# Thermistor_readout.net
KiCad netlist of a schematic drawn in EAGLE
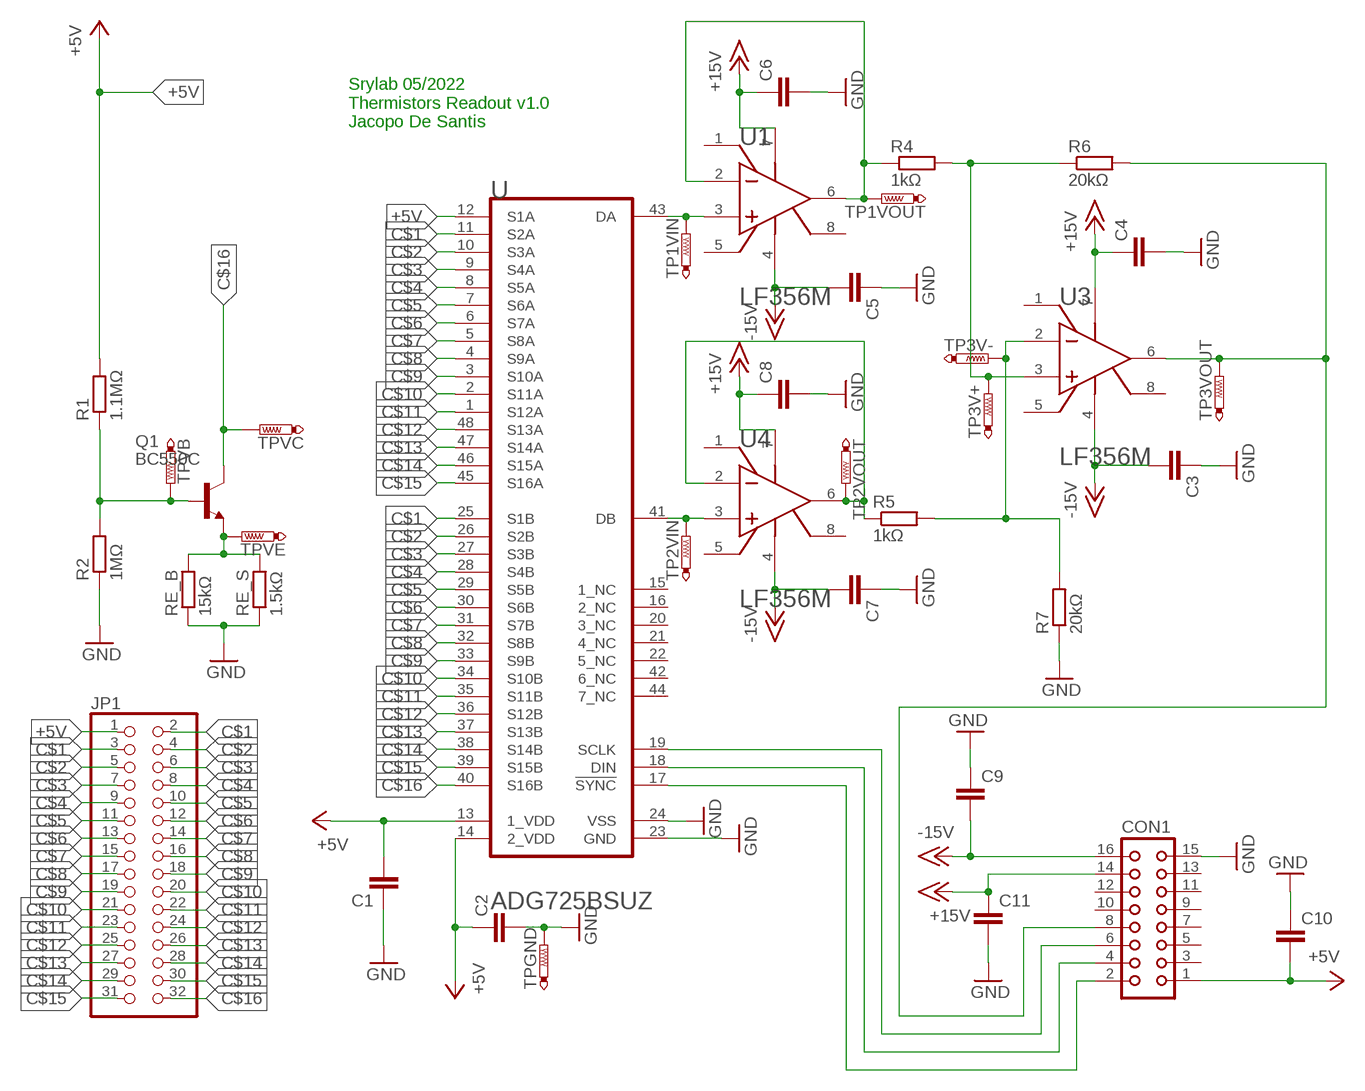
[diagram p0: schematic, sheet 1]

(export (version "E")
  (design (tool "Eeschema 10.0.6"))
  (components
    (comp (ref "C1")
      (value "C-EU_SMDR1206H")
      (footprint "eagle-import:R1206H")
      (libsource (lib "eagle-import") (part "C-EU_SMDR1206H"))
    )
    (comp (ref "C2")
      (value "C-EU_SMDR1206H")
      (footprint "eagle-import:R1206H")
      (libsource (lib "eagle-import") (part "C-EU_SMDR1206H"))
    )
    (comp (ref "C3")
      (value "C-EU_SMDR1206H")
      (footprint "eagle-import:R1206H")
      (libsource (lib "eagle-import") (part "C-EU_SMDR1206H"))
    )
    (comp (ref "C4")
      (value "C-EU_SMDR1206H")
      (footprint "eagle-import:R1206H")
      (libsource (lib "eagle-import") (part "C-EU_SMDR1206H"))
    )
    (comp (ref "C5")
      (value "C-EU_SMDR1206H")
      (footprint "eagle-import:R1206H")
      (libsource (lib "eagle-import") (part "C-EU_SMDR1206H"))
    )
    (comp (ref "C6")
      (value "C-EU_SMDR1206H")
      (footprint "eagle-import:R1206H")
      (libsource (lib "eagle-import") (part "C-EU_SMDR1206H"))
    )
    (comp (ref "C7")
      (value "C-EU_SMDR1206H")
      (footprint "eagle-import:R1206H")
      (libsource (lib "eagle-import") (part "C-EU_SMDR1206H"))
    )
    (comp (ref "C8")
      (value "C-EU_SMDR1206H")
      (footprint "eagle-import:R1206H")
      (libsource (lib "eagle-import") (part "C-EU_SMDR1206H"))
    )
    (comp (ref "C9")
      (value "C-EU_SMDC1206H/D")
      (footprint "eagle-import:C1206H_D")
      (libsource (lib "eagle-import") (part "C-EU_SMDC1206H/D"))
    )
    (comp (ref "C10")
      (value "C-EU_SMDC1206H/D")
      (footprint "eagle-import:C1206H_D")
      (libsource (lib "eagle-import") (part "C-EU_SMDC1206H/D"))
    )
    (comp (ref "C11")
      (value "C-EU_SMDC1206H/D")
      (footprint "eagle-import:C1206H_D")
      (libsource (lib "eagle-import") (part "C-EU_SMDC1206H/D"))
    )
    (comp (ref "CON1")
      (value "CON16L")
      (footprint "eagle-import:CON16L")
      (libsource (lib "eagle-import") (part "CON16L"))
    )
    (comp (ref "JP1")
      (value "PINHD-2X16")
      (footprint "eagle-import:2X16")
      (libsource (lib "eagle-import") (part "PINHD-2X16"))
    )
    (comp (ref "Q1")
      (value "BC550C")
      (footprint "eagle-import:TO92-EBC")
      (libsource (lib "eagle-import") (part "BC550C"))
    )
    (comp (ref "R1")
      (value "1.1ΜΩ")
      (footprint "eagle-import:R0805H")
      (libsource (lib "eagle-import") (part "R-EU_SMD0805H"))
    )
    (comp (ref "R2")
      (value "1ΜΩ")
      (footprint "eagle-import:R0805H")
      (libsource (lib "eagle-import") (part "R-EU_SMD0805H"))
    )
    (comp (ref "R4")
      (value "1kΩ")
      (footprint "eagle-import:R0805H")
      (libsource (lib "eagle-import") (part "R-EU_SMD0805H"))
    )
    (comp (ref "R5")
      (value "1kΩ")
      (footprint "eagle-import:R0805H")
      (libsource (lib "eagle-import") (part "R-EU_SMD0805H"))
    )
    (comp (ref "R6")
      (value "20kΩ")
      (footprint "eagle-import:R0805H")
      (libsource (lib "eagle-import") (part "R-EU_SMD0805H"))
    )
    (comp (ref "R7")
      (value "20kΩ")
      (footprint "eagle-import:R0805H")
      (libsource (lib "eagle-import") (part "R-EU_SMD0805H"))
    )
    (comp (ref "RE_B")
      (value "15kΩ")
      (footprint "eagle-import:R1206H")
      (libsource (lib "eagle-import") (part "R-EU_SMD1206H"))
    )
    (comp (ref "RE_S")
      (value "1.5kΩ")
      (footprint "eagle-import:R0805H")
      (libsource (lib "eagle-import") (part "R-EU_SMD0805H"))
    )
    (comp (ref "TP1VIN")
      (value "PTR1TP20R")
      (footprint "eagle-import:TP20R")
      (libsource (lib "eagle-import") (part "PTR1TP20R"))
    )
    (comp (ref "TP1VOUT")
      (value "PTR1TP20R")
      (footprint "eagle-import:TP20R")
      (libsource (lib "eagle-import") (part "PTR1TP20R"))
    )
    (comp (ref "TP2VIN")
      (value "PTR1TP20R")
      (footprint "eagle-import:TP20R")
      (libsource (lib "eagle-import") (part "PTR1TP20R"))
    )
    (comp (ref "TP2VOUT")
      (value "PTR1TP20R")
      (footprint "eagle-import:TP20R")
      (libsource (lib "eagle-import") (part "PTR1TP20R"))
    )
    (comp (ref "TP3V+")
      (value "PTR1TP20R")
      (footprint "eagle-import:TP20R")
      (libsource (lib "eagle-import") (part "PTR1TP20R"))
    )
    (comp (ref "TP3V-")
      (value "PTR1TP20R")
      (footprint "eagle-import:TP20R")
      (libsource (lib "eagle-import") (part "PTR1TP20R"))
    )
    (comp (ref "TP3VOUT")
      (value "PTR1TP20R")
      (footprint "eagle-import:TP20R")
      (libsource (lib "eagle-import") (part "PTR1TP20R"))
    )
    (comp (ref "TPGND")
      (value "PTR1TP20R")
      (footprint "eagle-import:TP20R")
      (libsource (lib "eagle-import") (part "PTR1TP20R"))
    )
    (comp (ref "TPVB")
      (value "PTR1TP20R")
      (footprint "eagle-import:TP20R")
      (libsource (lib "eagle-import") (part "PTR1TP20R"))
    )
    (comp (ref "TPVC")
      (value "PTR1TP20R")
      (footprint "eagle-import:TP20R")
      (libsource (lib "eagle-import") (part "PTR1TP20R"))
    )
    (comp (ref "TPVE")
      (value "PTR1TP20R")
      (footprint "eagle-import:TP20R")
      (libsource (lib "eagle-import") (part "PTR1TP20R"))
    )
    (comp (ref "U")
      (value "ANALOG_DEVICES_ADG725BSUZANALOG_DEVICES_ADG725BSUZ_0_2")
      (footprint "eagle-import:ANALOG_DEVICES_ADG725BSUZ_2")
      (fields (field (name "MF") "Analog Devices") (field (name "MPN") "ADG725BSUZ"))
      (libsource (lib "eagle-import") (part "ANALOG_DEVICES_ADG725BSUZANALOG_DEVICES_ADG725BSUZ_0_2"))
    )
    (comp (ref "U1")
      (value "TI_NATIONAL_SEMICONDUCTOR_LF356MTI_NATIONAL_SEMICONDUCTOR_LF356M_0_2")
      (footprint "eagle-import:TI_NATIONAL_SEMICONDUCTOR_LF356M_2")
      (fields (field (name "MF") "TI National Semiconductor") (field (name "MPN") "LF356M"))
      (libsource (lib "eagle-import") (part "TI_NATIONAL_SEMICONDUCTOR_LF356MTI_NATIONAL_SEMICONDUCTOR_LF356M_0_2"))
    )
    (comp (ref "U3")
      (value "TI_NATIONAL_SEMICONDUCTOR_LF356MTI_NATIONAL_SEMICONDUCTOR_LF356M_0_2")
      (footprint "eagle-import:TI_NATIONAL_SEMICONDUCTOR_LF356M_2")
      (fields (field (name "MF") "TI National Semiconductor") (field (name "MPN") "LF356M"))
      (libsource (lib "eagle-import") (part "TI_NATIONAL_SEMICONDUCTOR_LF356MTI_NATIONAL_SEMICONDUCTOR_LF356M_0_2"))
    )
    (comp (ref "U4")
      (value "TI_NATIONAL_SEMICONDUCTOR_LF356MTI_NATIONAL_SEMICONDUCTOR_LF356M_0_2")
      (footprint "eagle-import:TI_NATIONAL_SEMICONDUCTOR_LF356M_2")
      (fields (field (name "MF") "TI National Semiconductor") (field (name "MPN") "LF356M"))
      (libsource (lib "eagle-import") (part "TI_NATIONAL_SEMICONDUCTOR_LF356MTI_NATIONAL_SEMICONDUCTOR_LF356M_0_2"))
    )
  )
  (nets
    (net (code "1") (name "+5V") (class "Default")
      (node (ref "C1") (pin "2") (pinfunction "2_2") (pintype "passive"))
      (node (ref "C10") (pin "2") (pinfunction "2_2") (pintype "passive"))
      (node (ref "C2") (pin "1") (pinfunction "1_1") (pintype "passive"))
      (node (ref "CON1") (pin "1") (pinfunction "1_1") (pintype "passive"))
      (node (ref "JP1") (pin "1") (pinfunction "1_1") (pintype "passive"))
      (node (ref "R1") (pin "2") (pinfunction "2_2") (pintype "passive"))
      (node (ref "U") (pin "12") (pinfunction "S1A_12") (pintype "passive"))
      (node (ref "U") (pin "13") (pinfunction "1_VDD_13") (pintype "power_in"))
      (node (ref "U") (pin "14") (pinfunction "2_VDD_14") (pintype "power_in"))
    )
    (net (code "2") (name "+15V") (class "Default")
      (node (ref "C11") (pin "1") (pinfunction "1_1") (pintype "passive"))
      (node (ref "C4") (pin "1") (pinfunction "1_1") (pintype "passive"))
      (node (ref "C6") (pin "1") (pinfunction "1_1") (pintype "passive"))
      (node (ref "C8") (pin "1") (pinfunction "1_1") (pintype "passive"))
      (node (ref "CON1") (pin "14") (pinfunction "14_14") (pintype "passive"))
      (node (ref "U1") (pin "7") (pinfunction "V+_7") (pintype "power_in"))
      (node (ref "U3") (pin "7") (pinfunction "V+_7") (pintype "power_in"))
      (node (ref "U4") (pin "7") (pinfunction "V+_7") (pintype "power_in"))
    )
    (net (code "3") (name "-15V") (class "Default")
      (node (ref "C3") (pin "2") (pinfunction "2_2") (pintype "passive"))
      (node (ref "C5") (pin "2") (pinfunction "2_2") (pintype "passive"))
      (node (ref "C7") (pin "2") (pinfunction "2_2") (pintype "passive"))
      (node (ref "C9") (pin "2") (pinfunction "2_2") (pintype "passive"))
      (node (ref "CON1") (pin "16") (pinfunction "16_16") (pintype "passive"))
      (node (ref "U1") (pin "4") (pinfunction "V-_4") (pintype "power_in"))
      (node (ref "U3") (pin "4") (pinfunction "V-_4") (pintype "power_in"))
      (node (ref "U4") (pin "4") (pinfunction "V-_4") (pintype "power_in"))
    )
    (net (code "4") (name "C$1") (class "Default")
      (node (ref "JP1") (pin "2") (pinfunction "2_2") (pintype "passive"))
      (node (ref "JP1") (pin "3") (pinfunction "3_3") (pintype "passive"))
      (node (ref "U") (pin "11") (pinfunction "S2A_11") (pintype "passive"))
      (node (ref "U") (pin "25") (pinfunction "S1B_25") (pintype "passive"))
    )
    (net (code "5") (name "C$2") (class "Default")
      (node (ref "JP1") (pin "4") (pinfunction "4_4") (pintype "passive"))
      (node (ref "JP1") (pin "5") (pinfunction "5_5") (pintype "passive"))
      (node (ref "U") (pin "10") (pinfunction "S3A_10") (pintype "passive"))
      (node (ref "U") (pin "26") (pinfunction "S2B_26") (pintype "passive"))
    )
    (net (code "6") (name "C$3") (class "Default")
      (node (ref "JP1") (pin "6") (pinfunction "6_6") (pintype "passive"))
      (node (ref "JP1") (pin "7") (pinfunction "7_7") (pintype "passive"))
      (node (ref "U") (pin "27") (pinfunction "S3B_27") (pintype "passive"))
      (node (ref "U") (pin "9") (pinfunction "S4A_9") (pintype "passive"))
    )
    (net (code "7") (name "C$4") (class "Default")
      (node (ref "JP1") (pin "8") (pinfunction "8_8") (pintype "passive"))
      (node (ref "JP1") (pin "9") (pinfunction "9_9") (pintype "passive"))
      (node (ref "U") (pin "28") (pinfunction "S4B_28") (pintype "passive"))
      (node (ref "U") (pin "8") (pinfunction "S5A_8") (pintype "passive"))
    )
    (net (code "8") (name "C$5") (class "Default")
      (node (ref "JP1") (pin "10") (pinfunction "10_10") (pintype "passive"))
      (node (ref "JP1") (pin "11") (pinfunction "11_11") (pintype "passive"))
      (node (ref "U") (pin "29") (pinfunction "S5B_29") (pintype "passive"))
      (node (ref "U") (pin "7") (pinfunction "S6A_7") (pintype "passive"))
    )
    (net (code "9") (name "C$6") (class "Default")
      (node (ref "JP1") (pin "12") (pinfunction "12_12") (pintype "passive"))
      (node (ref "JP1") (pin "13") (pinfunction "13_13") (pintype "passive"))
      (node (ref "U") (pin "30") (pinfunction "S6B_30") (pintype "passive"))
      (node (ref "U") (pin "6") (pinfunction "S7A_6") (pintype "passive"))
    )
    (net (code "10") (name "C$7") (class "Default")
      (node (ref "JP1") (pin "14") (pinfunction "14_14") (pintype "passive"))
      (node (ref "JP1") (pin "15") (pinfunction "15_15") (pintype "passive"))
      (node (ref "U") (pin "31") (pinfunction "S7B_31") (pintype "passive"))
      (node (ref "U") (pin "5") (pinfunction "S8A_5") (pintype "passive"))
    )
    (net (code "11") (name "C$8") (class "Default")
      (node (ref "JP1") (pin "16") (pinfunction "16_16") (pintype "passive"))
      (node (ref "JP1") (pin "17") (pinfunction "17_17") (pintype "passive"))
      (node (ref "U") (pin "32") (pinfunction "S8B_32") (pintype "passive"))
      (node (ref "U") (pin "4") (pinfunction "S9A_4") (pintype "passive"))
    )
    (net (code "12") (name "C$9") (class "Default")
      (node (ref "JP1") (pin "18") (pinfunction "18_18") (pintype "passive"))
      (node (ref "JP1") (pin "19") (pinfunction "19_19") (pintype "passive"))
      (node (ref "U") (pin "3") (pinfunction "S10A_3") (pintype "passive"))
      (node (ref "U") (pin "33") (pinfunction "S9B_33") (pintype "passive"))
    )
    (net (code "13") (name "C$10") (class "Default")
      (node (ref "JP1") (pin "20") (pinfunction "20_20") (pintype "passive"))
      (node (ref "JP1") (pin "21") (pinfunction "21_21") (pintype "passive"))
      (node (ref "U") (pin "2") (pinfunction "S11A_2") (pintype "passive"))
      (node (ref "U") (pin "34") (pinfunction "S10B_34") (pintype "passive"))
    )
    (net (code "14") (name "C$11") (class "Default")
      (node (ref "JP1") (pin "22") (pinfunction "22_22") (pintype "passive"))
      (node (ref "JP1") (pin "23") (pinfunction "23_23") (pintype "passive"))
      (node (ref "U") (pin "1") (pinfunction "S12A_1") (pintype "passive"))
      (node (ref "U") (pin "35") (pinfunction "S11B_35") (pintype "passive"))
    )
    (net (code "15") (name "C$12") (class "Default")
      (node (ref "JP1") (pin "24") (pinfunction "24_24") (pintype "passive"))
      (node (ref "JP1") (pin "25") (pinfunction "25_25") (pintype "passive"))
      (node (ref "U") (pin "36") (pinfunction "S12B_36") (pintype "passive"))
      (node (ref "U") (pin "48") (pinfunction "S13A_48") (pintype "passive"))
    )
    (net (code "16") (name "C$13") (class "Default")
      (node (ref "JP1") (pin "26") (pinfunction "26_26") (pintype "passive"))
      (node (ref "JP1") (pin "27") (pinfunction "27_27") (pintype "passive"))
      (node (ref "U") (pin "37") (pinfunction "S13B_37") (pintype "passive"))
      (node (ref "U") (pin "47") (pinfunction "S14A_47") (pintype "passive"))
    )
    (net (code "17") (name "C$14") (class "Default")
      (node (ref "JP1") (pin "28") (pinfunction "28_28") (pintype "passive"))
      (node (ref "JP1") (pin "29") (pinfunction "29_29") (pintype "passive"))
      (node (ref "U") (pin "38") (pinfunction "S14B_38") (pintype "passive"))
      (node (ref "U") (pin "46") (pinfunction "S15A_46") (pintype "passive"))
    )
    (net (code "18") (name "C$15") (class "Default")
      (node (ref "JP1") (pin "30") (pinfunction "30_30") (pintype "passive"))
      (node (ref "JP1") (pin "31") (pinfunction "31_31") (pintype "passive"))
      (node (ref "U") (pin "39") (pinfunction "S15B_39") (pintype "passive"))
      (node (ref "U") (pin "45") (pinfunction "S16A_45") (pintype "passive"))
    )
    (net (code "19") (name "C$16") (class "Default")
      (node (ref "JP1") (pin "32") (pinfunction "32_32") (pintype "passive"))
      (node (ref "Q1") (pin "C") (pinfunction "C_C") (pintype "passive"))
      (node (ref "TPVC") (pin "TP") (pinfunction "TP_TP") (pintype "input"))
      (node (ref "U") (pin "40") (pinfunction "S16B_40") (pintype "passive"))
    )
    (net (code "20") (name "GND") (class "Default")
      (node (ref "C1") (pin "1") (pinfunction "1_1") (pintype "passive"))
      (node (ref "C10") (pin "1") (pinfunction "1_1") (pintype "passive"))
      (node (ref "C11") (pin "2") (pinfunction "2_2") (pintype "passive"))
      (node (ref "C2") (pin "2") (pinfunction "2_2") (pintype "passive"))
      (node (ref "C3") (pin "1") (pinfunction "1_1") (pintype "passive"))
      (node (ref "C4") (pin "2") (pinfunction "2_2") (pintype "passive"))
      (node (ref "C5") (pin "1") (pinfunction "1_1") (pintype "passive"))
      (node (ref "C6") (pin "2") (pinfunction "2_2") (pintype "passive"))
      (node (ref "C7") (pin "1") (pinfunction "1_1") (pintype "passive"))
      (node (ref "C8") (pin "2") (pinfunction "2_2") (pintype "passive"))
      (node (ref "C9") (pin "1") (pinfunction "1_1") (pintype "passive"))
      (node (ref "CON1") (pin "15") (pinfunction "15_15") (pintype "passive"))
      (node (ref "R2") (pin "1") (pinfunction "1_1") (pintype "passive"))
      (node (ref "R7") (pin "1") (pinfunction "1_1") (pintype "passive"))
      (node (ref "RE_B") (pin "1") (pinfunction "1_1") (pintype "passive"))
      (node (ref "RE_S") (pin "1") (pinfunction "1_1") (pintype "passive"))
      (node (ref "TPGND") (pin "TP") (pinfunction "TP_TP") (pintype "input"))
      (node (ref "U") (pin "23") (pinfunction "GND_23") (pintype "power_in"))
      (node (ref "U") (pin "24") (pinfunction "VSS_24") (pintype "power_in"))
    )
    (net (code "21") (name "Net-(Q1-PadB)") (class "Default")
      (node (ref "Q1") (pin "B") (pinfunction "B_B") (pintype "passive"))
      (node (ref "R1") (pin "1") (pinfunction "1_1") (pintype "passive"))
      (node (ref "R2") (pin "2") (pinfunction "2_2") (pintype "passive"))
      (node (ref "TPVB") (pin "TP") (pinfunction "TP_TP") (pintype "input"))
    )
    (net (code "22") (name "Net-(Q1-PadE)") (class "Default")
      (node (ref "Q1") (pin "E") (pinfunction "E_E") (pintype "passive"))
      (node (ref "RE_B") (pin "2") (pinfunction "2_2") (pintype "passive"))
      (node (ref "RE_S") (pin "2") (pinfunction "2_2") (pintype "passive"))
      (node (ref "TPVE") (pin "TP") (pinfunction "TP_TP") (pintype "input"))
    )
    (net (code "23") (name "Net-(U-DA)") (class "Default")
      (node (ref "TP1VIN") (pin "TP") (pinfunction "TP_TP") (pintype "input"))
      (node (ref "U") (pin "43") (pinfunction "DA_43") (pintype "passive"))
      (node (ref "U1") (pin "3") (pinfunction "IN+_3") (pintype "input"))
    )
    (net (code "24") (name "Net-(U-DB)") (class "Default")
      (node (ref "TP2VIN") (pin "TP") (pinfunction "TP_TP") (pintype "input"))
      (node (ref "U") (pin "41") (pinfunction "DB_41") (pintype "passive"))
      (node (ref "U4") (pin "3") (pinfunction "IN+_3") (pintype "input"))
    )
    (net (code "25") (name "Net-(U-DIN)") (class "Default")
      (node (ref "CON1") (pin "4") (pinfunction "4_4") (pintype "passive"))
      (node (ref "U") (pin "18") (pinfunction "DIN_18") (pintype "input"))
    )
    (net (code "26") (name "Net-(U-SCLK)") (class "Default")
      (node (ref "CON1") (pin "6") (pinfunction "6_6") (pintype "passive"))
      (node (ref "U") (pin "19") (pinfunction "SCLK_19") (pintype "input"))
    )
    (net (code "27") (name "Net-(U-~{SYNC})") (class "Default")
      (node (ref "CON1") (pin "2") (pinfunction "2_2") (pintype "passive"))
      (node (ref "U") (pin "17") (pinfunction "~{SYNC}_17") (pintype "input"))
    )
    (net (code "28") (name "Net-(U1-IN-)") (class "Default")
      (node (ref "R4") (pin "1") (pinfunction "1_1") (pintype "passive"))
      (node (ref "TP1VOUT") (pin "TP") (pinfunction "TP_TP") (pintype "input"))
      (node (ref "U1") (pin "2") (pinfunction "IN-_2") (pintype "input"))
      (node (ref "U1") (pin "6") (pinfunction "OUT_6") (pintype "output"))
    )
    (net (code "29") (name "Net-(U3-IN+)") (class "Default")
      (node (ref "R4") (pin "2") (pinfunction "2_2") (pintype "passive"))
      (node (ref "R6") (pin "1") (pinfunction "1_1") (pintype "passive"))
      (node (ref "TP3V+") (pin "TP") (pinfunction "TP_TP") (pintype "input"))
      (node (ref "U3") (pin "3") (pinfunction "IN+_3") (pintype "input"))
    )
    (net (code "30") (name "Net-(U3-IN-)") (class "Default")
      (node (ref "R5") (pin "2") (pinfunction "2_2") (pintype "passive"))
      (node (ref "R7") (pin "2") (pinfunction "2_2") (pintype "passive"))
      (node (ref "TP3V-") (pin "TP") (pinfunction "TP_TP") (pintype "input"))
      (node (ref "U3") (pin "2") (pinfunction "IN-_2") (pintype "input"))
    )
    (net (code "31") (name "Net-(U3-OUT)") (class "Default")
      (node (ref "CON1") (pin "8") (pinfunction "8_8") (pintype "passive"))
      (node (ref "R6") (pin "2") (pinfunction "2_2") (pintype "passive"))
      (node (ref "TP3VOUT") (pin "TP") (pinfunction "TP_TP") (pintype "input"))
      (node (ref "U3") (pin "6") (pinfunction "OUT_6") (pintype "output"))
    )
    (net (code "32") (name "Net-(U4-IN-)") (class "Default")
      (node (ref "R5") (pin "1") (pinfunction "1_1") (pintype "passive"))
      (node (ref "TP2VOUT") (pin "TP") (pinfunction "TP_TP") (pintype "input"))
      (node (ref "U4") (pin "2") (pinfunction "IN-_2") (pintype "input"))
      (node (ref "U4") (pin "6") (pinfunction "OUT_6") (pintype "output"))
    )
    (net (code "33") (name "unconnected-(CON1-Pad3)") (class "Default")
      (node (ref "CON1") (pin "3") (pinfunction "3_3") (pintype "passive"))
    )
    (net (code "34") (name "unconnected-(CON1-Pad5)") (class "Default")
      (node (ref "CON1") (pin "5") (pinfunction "5_5") (pintype "passive"))
    )
    (net (code "35") (name "unconnected-(CON1-Pad7)") (class "Default")
      (node (ref "CON1") (pin "7") (pinfunction "7_7") (pintype "passive"))
    )
    (net (code "36") (name "unconnected-(CON1-Pad9)") (class "Default")
      (node (ref "CON1") (pin "9") (pinfunction "9_9") (pintype "passive"))
    )
    (net (code "37") (name "unconnected-(CON1-Pad10)") (class "Default")
      (node (ref "CON1") (pin "10") (pinfunction "10_10") (pintype "passive"))
    )
    (net (code "38") (name "unconnected-(CON1-Pad11)") (class "Default")
      (node (ref "CON1") (pin "11") (pinfunction "11_11") (pintype "passive"))
    )
    (net (code "39") (name "unconnected-(CON1-Pad12)") (class "Default")
      (node (ref "CON1") (pin "12") (pinfunction "12_12") (pintype "passive"))
    )
    (net (code "40") (name "unconnected-(CON1-Pad13)") (class "Default")
      (node (ref "CON1") (pin "13") (pinfunction "13_13") (pintype "passive"))
    )
    (net (code "41") (name "unconnected-(U-1_NC-Pad15)") (class "Default")
      (node (ref "U") (pin "15") (pinfunction "1_NC_15") (pintype "passive"))
    )
    (net (code "42") (name "unconnected-(U-2_NC-Pad16)") (class "Default")
      (node (ref "U") (pin "16") (pinfunction "2_NC_16") (pintype "passive"))
    )
    (net (code "43") (name "unconnected-(U-3_NC-Pad20)") (class "Default")
      (node (ref "U") (pin "20") (pinfunction "3_NC_20") (pintype "passive"))
    )
    (net (code "44") (name "unconnected-(U-4_NC-Pad21)") (class "Default")
      (node (ref "U") (pin "21") (pinfunction "4_NC_21") (pintype "passive"))
    )
    (net (code "45") (name "unconnected-(U-5_NC-Pad22)") (class "Default")
      (node (ref "U") (pin "22") (pinfunction "5_NC_22") (pintype "passive"))
    )
    (net (code "46") (name "unconnected-(U-6_NC-Pad42)") (class "Default")
      (node (ref "U") (pin "42") (pinfunction "6_NC_42") (pintype "passive"))
    )
    (net (code "47") (name "unconnected-(U-7_NC-Pad44)") (class "Default")
      (node (ref "U") (pin "44") (pinfunction "7_NC_44") (pintype "passive"))
    )
    (net (code "48") (name "unconnected-(U1-1_BAL-Pad1)") (class "Default")
      (node (ref "U1") (pin "1") (pinfunction "1_BAL_1") (pintype "passive"))
    )
    (net (code "49") (name "unconnected-(U1-2_BAL-Pad5)") (class "Default")
      (node (ref "U1") (pin "5") (pinfunction "2_BAL_5") (pintype "passive"))
    )
    (net (code "50") (name "unconnected-(U1-NC-Pad8)") (class "Default")
      (node (ref "U1") (pin "8") (pinfunction "NC_8") (pintype "passive"))
    )
    (net (code "51") (name "unconnected-(U3-1_BAL-Pad1)") (class "Default")
      (node (ref "U3") (pin "1") (pinfunction "1_BAL_1") (pintype "passive"))
    )
    (net (code "52") (name "unconnected-(U3-2_BAL-Pad5)") (class "Default")
      (node (ref "U3") (pin "5") (pinfunction "2_BAL_5") (pintype "passive"))
    )
    (net (code "53") (name "unconnected-(U3-NC-Pad8)") (class "Default")
      (node (ref "U3") (pin "8") (pinfunction "NC_8") (pintype "passive"))
    )
    (net (code "54") (name "unconnected-(U4-1_BAL-Pad1)") (class "Default")
      (node (ref "U4") (pin "1") (pinfunction "1_BAL_1") (pintype "passive"))
    )
    (net (code "55") (name "unconnected-(U4-2_BAL-Pad5)") (class "Default")
      (node (ref "U4") (pin "5") (pinfunction "2_BAL_5") (pintype "passive"))
    )
    (net (code "56") (name "unconnected-(U4-NC-Pad8)") (class "Default")
      (node (ref "U4") (pin "8") (pinfunction "NC_8") (pintype "passive"))
    )
  )
)
